# Digital_Encoder_Breakout.net
KiCad netlist of a schematic drawn in Altium Designer
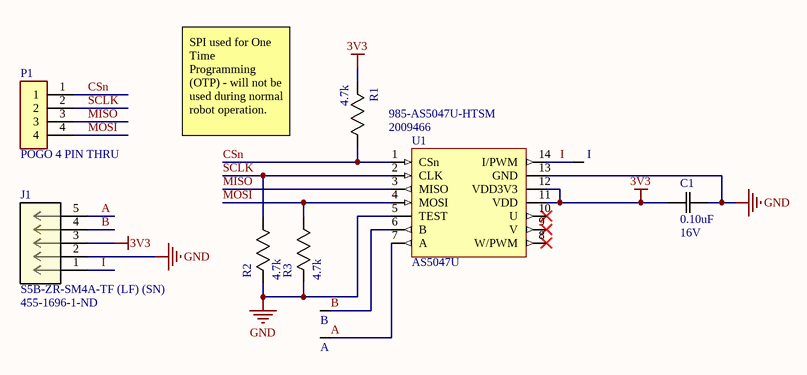
[diagram p0: Digital_Encoder_Breakout.SchDoc]

(export (version "E")
  (design (tool "Eeschema 10.0.6"))
  (components
    (comp (ref "A")
      (value "Test Point (Via)")
      (footprint "TP")
      (libsource (lib "AltiumLibraries") (part "Test Point (Via)"))
    )
    (comp (ref "B")
      (value "Test Point (Via)")
      (footprint "TP")
      (libsource (lib "AltiumLibraries") (part "Test Point (Via)"))
    )
    (comp (ref "C1")
      (value "0.10uF")
      (footprint "0603")
      (description "CAP CER 0.10UF 16V X5R 0603/0805")
      (fields (field (name "TOLERANCE") "10%") (field (name "RATING") "16V"))
      (libsource (lib "AltiumLibraries") (part "CAP 0.10uF 16V"))
    )
    (comp (ref "I")
      (value "Test Point (Via)")
      (footprint "TP")
      (libsource (lib "AltiumLibraries") (part "Test Point (Via)"))
    )
    (comp (ref "J1")
      (value "S5B-ZR-SM4A-TF (LF) (SN)")
      (footprint "CONN_S5B-ZR-SM4A-TF_JST")
      (description "Connector Header Surface Mount, Right Angle 5 position 0.059\" (1.50mm)")
      (fields
        (field (name "SUPPLIER PART NUMBER 1") "455-1696-1-ND")
        (field (name "COPYRIGHT") "Copyright (C) 2021 Ultra Librarian. All rights reserved.")
      )
      (libsource (lib "AltiumLibraries") (part "CN 4POS JST ZH"))
    )
    (comp (ref "P1")
      (value "POGO 4 PIN THRU")
      (footprint "POGO 4 PIN THRU")
      (description "4 pin POGO Holes 0.100\" Pitch")
      (libsource (lib "AltiumLibraries") (part "POGO 4 PIN THRU"))
    )
    (comp (ref "R1")
      (value "4.7k")
      (footprint "0603")
      (description "RES SMD 4.7k OHM 5% 1/8W 0805")
      (fields (field (name "TOLERANCE") "5%"))
      (libsource (lib "") (part "RES 4.7k 1/8W - 5%_1"))
    )
    (comp (ref "R2")
      (value "4.7k")
      (footprint "0603")
      (description "RES SMD 4.7k OHM 5% 1/8W 0805")
      (fields (field (name "TOLERANCE") "5%"))
      (libsource (lib "") (part "RES 4.7k 1/8W - 5%_1"))
    )
    (comp (ref "R3")
      (value "4.7k")
      (footprint "0603")
      (description "RES SMD 4.7k OHM 5% 1/8W 0805")
      (fields (field (name "TOLERANCE") "5%"))
      (libsource (lib "AltiumLibraries") (part "RES 4.7k 1/8W - 5%"))
    )
    (comp (ref "U1")
      (value "AS5047U")
      (footprint "AS5047U")
      (description "14-Bit On-Axis Magnetic Rotary Position Sensor with Up to 14-Bit Binary Incremental Pulse Count")
      (fields
        (field (name "SUPPLIER PART NUMBER 1") "2009466")
        (field (name "SUPPLIER PART NUMBER 2") "985-AS5047U-HTSM")
      )
      (libsource (lib "AltiumLibraries") (part "AS5047U"))
    )
  )
  (nets
    (net (code "1") (name "/A") (class "Default")
      (node (ref "A") (pin "1") (pinfunction "1_1") (pintype "passive"))
      (node (ref "J1") (pin "5") (pinfunction "5_5") (pintype "passive"))
      (node (ref "U1") (pin "7") (pinfunction "A_7") (pintype "output"))
    )
    (net (code "2") (name "/B") (class "Default")
      (node (ref "B") (pin "1") (pinfunction "1_1") (pintype "passive"))
      (node (ref "J1") (pin "4") (pinfunction "4_4") (pintype "passive"))
      (node (ref "U1") (pin "6") (pinfunction "B_6") (pintype "output"))
    )
    (net (code "3") (name "/CSn") (class "Default")
      (node (ref "P1") (pin "1") (pinfunction "1_1") (pintype "passive"))
      (node (ref "R1") (pin "1") (pinfunction "R1_1") (pintype "passive"))
      (node (ref "U1") (pin "1") (pinfunction "CSn_1") (pintype "input"))
    )
    (net (code "4") (name "/I") (class "Default")
      (node (ref "I") (pin "1") (pinfunction "1_1") (pintype "passive"))
      (node (ref "J1") (pin "1") (pinfunction "1_1") (pintype "passive"))
      (node (ref "U1") (pin "14") (pinfunction "I/PWM_14") (pintype "output"))
    )
    (net (code "5") (name "/MISO") (class "Default")
      (node (ref "P1") (pin "3") (pinfunction "3_3") (pintype "passive"))
      (node (ref "U1") (pin "3") (pinfunction "MISO_3") (pintype "output"))
    )
    (net (code "6") (name "/MOSI") (class "Default")
      (node (ref "P1") (pin "4") (pinfunction "4_4") (pintype "passive"))
      (node (ref "R3") (pin "1") (pinfunction "R1_1") (pintype "passive"))
      (node (ref "U1") (pin "4") (pinfunction "MOSI_4") (pintype "input"))
    )
    (net (code "7") (name "/SCLK") (class "Default")
      (node (ref "P1") (pin "2") (pinfunction "2_2") (pintype "passive"))
      (node (ref "R2") (pin "1") (pinfunction "R1_1") (pintype "passive"))
      (node (ref "U1") (pin "2") (pinfunction "CLK_2") (pintype "input"))
    )
    (net (code "8") (name "3V3") (class "Default")
      (node (ref "C1") (pin "1") (pinfunction "C1_1") (pintype "passive"))
      (node (ref "J1") (pin "3") (pinfunction "3_3") (pintype "passive"))
      (node (ref "R1") (pin "2") (pinfunction "R2_2") (pintype "passive"))
      (node (ref "U1") (pin "11") (pinfunction "VDD_11") (pintype "passive"))
      (node (ref "U1") (pin "12") (pinfunction "VDD3V3_12") (pintype "passive"))
    )
    (net (code "9") (name "GND") (class "Default")
      (node (ref "C1") (pin "2") (pinfunction "C2_2") (pintype "passive"))
      (node (ref "J1") (pin "2") (pinfunction "2_2") (pintype "passive"))
      (node (ref "R2") (pin "2") (pinfunction "R2_2") (pintype "passive"))
      (node (ref "R3") (pin "2") (pinfunction "R2_2") (pintype "passive"))
      (node (ref "U1") (pin "13") (pinfunction "GND_13") (pintype "passive"))
      (node (ref "U1") (pin "5") (pinfunction "TEST_5") (pintype "passive"))
    )
    (net (code "10") (name "unconnected-(U1-U-Pad10)") (class "Default")
      (node (ref "U1") (pin "10") (pinfunction "U_10") (pintype "output+no_connect"))
    )
    (net (code "11") (name "unconnected-(U1-V-Pad9)") (class "Default")
      (node (ref "U1") (pin "9") (pinfunction "V_9") (pintype "output+no_connect"))
    )
    (net (code "12") (name "unconnected-(U1-W{slash}PWM-Pad8)") (class "Default")
      (node (ref "U1") (pin "8") (pinfunction "W/PWM_8") (pintype "output+no_connect"))
    )
  )
)
